# 232_CAN.net
KiCad netlist of a schematic drawn in Altium Designer
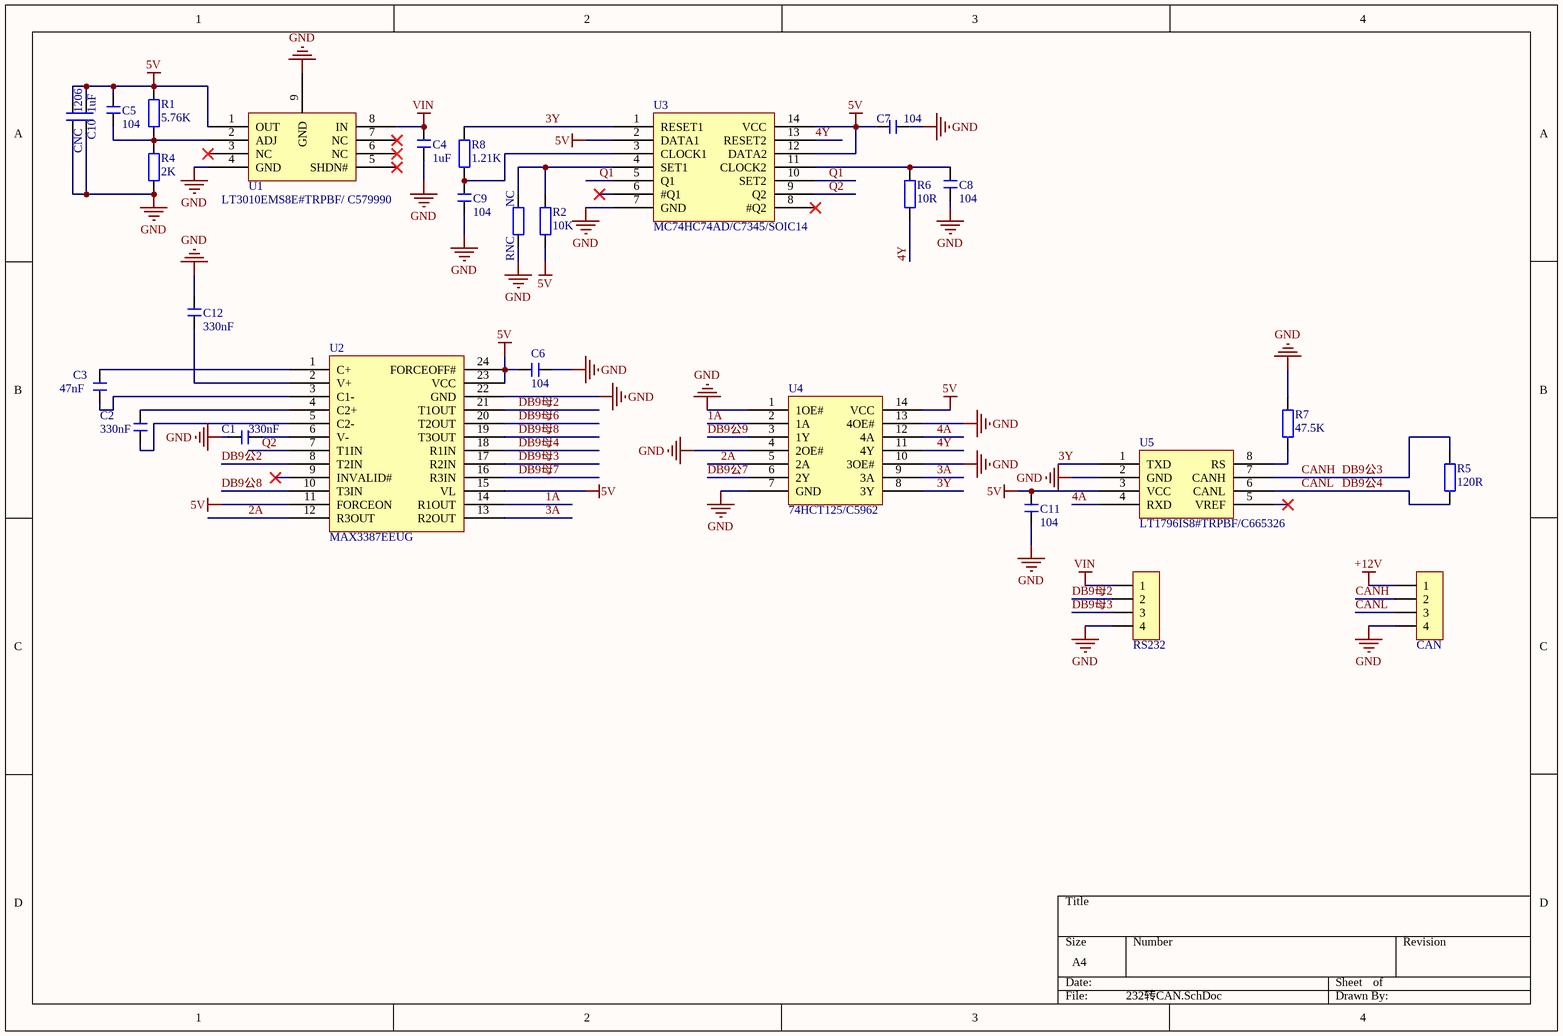
[diagram p0: 232转CAN.SchDoc]

(export (version "E")
  (design (tool "Eeschema 10.0.6"))
  (components
    (comp (ref "C1")
      (value "330nF")
      (footprint "C0603_L")
      (description "独石电容")
      (fields (field (name "版权归属") "封装库来自淘宝 ID：黄晶宝石"))
      (libsource (lib "0.1 - 电阻-电容-电感") (part "C-MLCC"))
    )
    (comp (ref "C2")
      (value "330nF")
      (footprint "C0603_L")
      (description "独石电容")
      (fields (field (name "版权归属") "封装库来自淘宝 ID：黄晶宝石"))
      (libsource (lib "0.1 - 电阻-电容-电感") (part "C-MLCC"))
    )
    (comp (ref "C3")
      (value "47nF")
      (footprint "C0603_L")
      (description "独石电容")
      (fields (field (name "版权归属") "封装库来自淘宝 ID：黄晶宝石"))
      (libsource (lib "0.1 - 电阻-电容-电感") (part "C-MLCC"))
    )
    (comp (ref "C4")
      (value "1uF")
      (footprint "C0603_L")
      (description "独石电容")
      (fields (field (name "版权归属") "封装库来自淘宝 ID：黄晶宝石"))
      (libsource (lib "0.1 - 电阻-电容-电感") (part "C-MLCC"))
    )
    (comp (ref "C5")
      (value "104")
      (footprint "C0603_L")
      (description "贴片电容")
      (libsource (lib "0.1 - 电阻-电容-电感") (part "C"))
    )
    (comp (ref "C6")
      (value "104")
      (footprint "C0603_L")
      (description "独石电容")
      (fields (field (name "版权归属") "封装库来自淘宝 ID：黄晶宝石"))
      (libsource (lib "0.1 - 电阻-电容-电感") (part "C-MLCC"))
    )
    (comp (ref "C7")
      (value "104")
      (footprint "C0603_L")
      (description "独石电容")
      (fields (field (name "版权归属") "封装库来自淘宝 ID：黄晶宝石"))
      (libsource (lib "0.1 - 电阻-电容-电感") (part "C-MLCC"))
    )
    (comp (ref "C8")
      (value "104")
      (footprint "C0603_L")
      (description "独石电容")
      (fields (field (name "版权归属") "封装库来自淘宝 ID：黄晶宝石"))
      (libsource (lib "0.1 - 电阻-电容-电感") (part "C-MLCC"))
    )
    (comp (ref "C9")
      (value "104")
      (footprint "C0603_L")
      (description "独石电容")
      (fields (field (name "版权归属") "封装库来自淘宝 ID：黄晶宝石"))
      (libsource (lib "0.1 - 电阻-电容-电感") (part "C-MLCC"))
    )
    (comp (ref "C10")
      (value "1uF")
      (footprint "C0603_L")
      (description "独石电容")
      (fields (field (name "版权归属") "封装库来自淘宝 ID：黄晶宝石"))
      (libsource (lib "0.1 - 电阻-电容-电感") (part "C-MLCC"))
    )
    (comp (ref "C11")
      (value "104")
      (footprint "C0603_L")
      (description "独石电容")
      (fields (field (name "版权归属") "封装库来自淘宝 ID：黄晶宝石"))
      (libsource (lib "0.1 - 电阻-电容-电感") (part "C-MLCC"))
    )
    (comp (ref "C12")
      (value "330nF")
      (footprint "C0603_L")
      (description "独石电容")
      (fields (field (name "版权归属") "封装库来自淘宝 ID：黄晶宝石"))
      (libsource (lib "0.1 - 电阻-电容-电感") (part "C-MLCC"))
    )
    (comp (ref "CAN")
      (value "HDR-1X4")
      (footprint "HDR2.54-LI-4P")
      (description "4P接插件")
      (fields (field (name "版权归属") "封装库来自淘宝 ID：黄晶宝石"))
      (libsource (lib "5.4 - 接插件-脚距2.54 (100mil) ") (part "Header 4"))
    )
    (comp (ref "CNC")
      (value "1206")
      (footprint "C1206_L")
      (description "独石电容")
      (fields (field (name "版权归属") "封装库来自淘宝 ID：黄晶宝石"))
      (libsource (lib "0.1 - 电阻-电容-电感") (part "C-MLCC"))
    )
    (comp (ref "R1")
      (value "5.76K")
      (footprint "R0603_L")
      (description "贴片电阻")
      (fields (field (name "版权归属") "来自淘宝 ID：黄晶宝石"))
      (libsource (lib "0.1 - 电阻-电容-电感") (part "R"))
    )
    (comp (ref "R2")
      (value "10K")
      (footprint "R0603_L")
      (description "贴片电阻")
      (fields (field (name "版权归属") "来自淘宝 ID：黄晶宝石"))
      (libsource (lib "0.1 - 电阻-电容-电感") (part "R"))
    )
    (comp (ref "R4")
      (value "2K")
      (footprint "R0603_L")
      (description "贴片电阻")
      (fields (field (name "版权归属") "来自淘宝 ID：黄晶宝石"))
      (libsource (lib "0.1 - 电阻-电容-电感") (part "R"))
    )
    (comp (ref "R5")
      (value "120R")
      (footprint "R0603_L")
      (description "贴片电阻")
      (fields (field (name "版权归属") "来自淘宝 ID：黄晶宝石"))
      (libsource (lib "0.1 - 电阻-电容-电感") (part "R"))
    )
    (comp (ref "R6")
      (value "10R")
      (footprint "R0603_L")
      (description "贴片电阻")
      (fields (field (name "版权归属") "来自淘宝 ID：黄晶宝石"))
      (libsource (lib "0.1 - 电阻-电容-电感") (part "R"))
    )
    (comp (ref "R7")
      (value "47.5K")
      (footprint "R0603_L")
      (description "贴片电阻")
      (fields (field (name "版权归属") "来自淘宝 ID：黄晶宝石"))
      (libsource (lib "0.1 - 电阻-电容-电感") (part "R"))
    )
    (comp (ref "R8")
      (value "1.21K")
      (footprint "R0603_L")
      (description "贴片电阻")
      (fields (field (name "版权归属") "来自淘宝 ID：黄晶宝石"))
      (libsource (lib "0.1 - 电阻-电容-电感") (part "R"))
    )
    (comp (ref "RNC")
      (value "NC")
      (footprint "R0603_L")
      (description "贴片电阻")
      (fields (field (name "版权归属") "来自淘宝 ID：黄晶宝石"))
      (libsource (lib "0.1 - 电阻-电容-电感") (part "R"))
    )
    (comp (ref "RS232")
      (value "HDR-1X4")
      (footprint "HDR2.54-LI-4P")
      (description "4P接插件")
      (fields (field (name "版权归属") "封装库来自淘宝 ID：黄晶宝石"))
      (libsource (lib "5.4 - 接插件-脚距2.54 (100mil) ") (part "Header 4"))
    )
    (comp (ref "U1")
      (value "LT3010EMS8E#TRPBF/ C579990")
      (footprint "LT3010EMS8E#TRPBF/sop8-ep")
      (libsource (lib "232转CAN") (part "LT3010EMS8E#TRPBF/ C579990"))
    )
    (comp (ref "U2")
      (value "MAX3387EEUG")
      (footprint "MAX3387EEUG/tssop24")
      (libsource (lib "232转CAN") (part "MAX3387EEUG"))
    )
    (comp (ref "U3")
      (value "MC74HC74AD/C7345/SOIC14")
      (footprint "74HCT125/SOIC14")
      (libsource (lib "232转CAN") (part "MC74HC74AD/C7345/SOIC14"))
    )
    (comp (ref "U4")
      (value "74HCT125/C5962")
      (footprint "74HCT125/SOIC14")
      (libsource (lib "232转CAN") (part "74HCT125/C5962"))
    )
    (comp (ref "U5")
      (value "LT1796IS8#TRPBF/C665326")
      (footprint "LT1796IS8#TRPBF/C665326")
      (libsource (lib "232转CAN") (part "LT1796IS8#TRPBF/C665326"))
    )
  )
  (nets
    (net (code "1") (name "+12V") (class "Default")
      (node (ref "CAN") (pin "1") (pinfunction "1_1") (pintype "passive"))
    )
    (net (code "2") (name "/1A") (class "Default")
      (node (ref "U2") (pin "14") (pinfunction "R1OUT_14") (pintype "passive"))
      (node (ref "U4") (pin "2") (pinfunction "1A_2") (pintype "passive"))
    )
    (net (code "3") (name "/2A") (class "Default")
      (node (ref "U2") (pin "12") (pinfunction "R3OUT_12") (pintype "passive"))
      (node (ref "U4") (pin "5") (pinfunction "2A_5") (pintype "passive"))
    )
    (net (code "4") (name "/3A") (class "Default")
      (node (ref "U2") (pin "13") (pinfunction "R2OUT_13") (pintype "passive"))
      (node (ref "U4") (pin "9") (pinfunction "3A_9") (pintype "passive"))
    )
    (net (code "5") (name "/3Y") (class "Default")
      (node (ref "R8") (pin "1") (pinfunction "1_1") (pintype "passive"))
      (node (ref "U3") (pin "1") (pinfunction "RESET1_1") (pintype "passive"))
      (node (ref "U4") (pin "8") (pinfunction "3Y_8") (pintype "passive"))
      (node (ref "U5") (pin "1") (pinfunction "TXD_1") (pintype "passive"))
    )
    (net (code "6") (name "/4A") (class "Default")
      (node (ref "U4") (pin "12") (pinfunction "4A_12") (pintype "passive"))
      (node (ref "U5") (pin "4") (pinfunction "RXD_4") (pintype "passive"))
    )
    (net (code "7") (name "/4Y") (class "Default")
      (node (ref "R6") (pin "2") (pinfunction "2_2") (pintype "passive"))
      (node (ref "U3") (pin "13") (pinfunction "RESET2_13") (pintype "passive"))
      (node (ref "U4") (pin "11") (pinfunction "4Y_11") (pintype "passive"))
    )
    (net (code "8") (name "/CANH") (class "Default")
      (node (ref "CAN") (pin "2") (pinfunction "2_2") (pintype "passive"))
      (node (ref "R5") (pin "1") (pinfunction "1_1") (pintype "passive"))
      (node (ref "U5") (pin "7") (pinfunction "CANH_7") (pintype "passive"))
    )
    (net (code "9") (name "/CANL") (class "Default")
      (node (ref "CAN") (pin "3") (pinfunction "3_3") (pintype "passive"))
      (node (ref "R5") (pin "2") (pinfunction "2_2") (pintype "passive"))
      (node (ref "U5") (pin "6") (pinfunction "CANL_6") (pintype "passive"))
    )
    (net (code "10") (name "/DB9公2") (class "Default")
      (node (ref "U2") (pin "8") (pinfunction "T2IN_8") (pintype "passive"))
    )
    (net (code "11") (name "/DB9公7") (class "Default")
      (node (ref "U4") (pin "6") (pinfunction "2Y_6") (pintype "passive"))
    )
    (net (code "12") (name "/DB9公8") (class "Default")
      (node (ref "U2") (pin "10") (pinfunction "T3IN_10") (pintype "passive"))
    )
    (net (code "13") (name "/DB9公9") (class "Default")
      (node (ref "U4") (pin "3") (pinfunction "1Y_3") (pintype "passive"))
    )
    (net (code "14") (name "/DB9母2") (class "Default")
      (node (ref "RS232") (pin "2") (pinfunction "2_2") (pintype "passive"))
      (node (ref "U2") (pin "21") (pinfunction "T1OUT_21") (pintype "passive"))
    )
    (net (code "15") (name "/DB9母3") (class "Default")
      (node (ref "RS232") (pin "3") (pinfunction "3_3") (pintype "passive"))
      (node (ref "U2") (pin "17") (pinfunction "R2IN_17") (pintype "passive"))
    )
    (net (code "16") (name "/DB9母4") (class "Default")
      (node (ref "U2") (pin "18") (pinfunction "R1IN_18") (pintype "passive"))
    )
    (net (code "17") (name "/DB9母6") (class "Default")
      (node (ref "U2") (pin "20") (pinfunction "T2OUT_20") (pintype "passive"))
    )
    (net (code "18") (name "/DB9母7") (class "Default")
      (node (ref "U2") (pin "16") (pinfunction "R3IN_16") (pintype "passive"))
    )
    (net (code "19") (name "/DB9母8") (class "Default")
      (node (ref "U2") (pin "19") (pinfunction "T3OUT_19") (pintype "passive"))
    )
    (net (code "20") (name "/Q1") (class "Default")
      (node (ref "U3") (pin "10") (pinfunction "SET2_10") (pintype "passive"))
      (node (ref "U3") (pin "5") (pinfunction "Q1_5") (pintype "passive"))
    )
    (net (code "21") (name "/Q2") (class "Default")
      (node (ref "U2") (pin "7") (pinfunction "T1IN_7") (pintype "passive"))
      (node (ref "U3") (pin "9") (pinfunction "Q2_9") (pintype "passive"))
    )
    (net (code "22") (name "5V") (class "Default")
      (node (ref "C10") (pin "2") (pinfunction "2_2") (pintype "passive"))
      (node (ref "C11") (pin "1") (pinfunction "1_1") (pintype "passive"))
      (node (ref "C5") (pin "2") (pinfunction "2_2") (pintype "passive"))
      (node (ref "C6") (pin "2") (pinfunction "2_2") (pintype "passive"))
      (node (ref "C7") (pin "1") (pinfunction "1_1") (pintype "passive"))
      (node (ref "CNC") (pin "2") (pinfunction "2_2") (pintype "passive"))
      (node (ref "R1") (pin "2") (pinfunction "2_2") (pintype "passive"))
      (node (ref "R2") (pin "2") (pinfunction "2_2") (pintype "passive"))
      (node (ref "U1") (pin "1") (pinfunction "OUT_1") (pintype "passive"))
      (node (ref "U2") (pin "11") (pinfunction "FORCEON_11") (pintype "passive"))
      (node (ref "U2") (pin "15") (pinfunction "VL_15") (pintype "passive"))
      (node (ref "U2") (pin "23") (pinfunction "VCC_23") (pintype "passive"))
      (node (ref "U2") (pin "24") (pinfunction "FORCEOFF#_24") (pintype "passive"))
      (node (ref "U3") (pin "12") (pinfunction "DATA2_12") (pintype "passive"))
      (node (ref "U3") (pin "14") (pinfunction "VCC_14") (pintype "passive"))
      (node (ref "U3") (pin "2") (pinfunction "DATA1_2") (pintype "passive"))
      (node (ref "U4") (pin "14") (pinfunction "VCC_14") (pintype "passive"))
      (node (ref "U5") (pin "3") (pinfunction "VCC_3") (pintype "passive"))
    )
    (net (code "23") (name "GND") (class "Default")
      (node (ref "C1") (pin "2") (pinfunction "2_2") (pintype "passive"))
      (node (ref "C10") (pin "1") (pinfunction "1_1") (pintype "passive"))
      (node (ref "C11") (pin "2") (pinfunction "2_2") (pintype "passive"))
      (node (ref "C12") (pin "2") (pinfunction "2_2") (pintype "passive"))
      (node (ref "C4") (pin "1") (pinfunction "1_1") (pintype "passive"))
      (node (ref "C6") (pin "1") (pinfunction "1_1") (pintype "passive"))
      (node (ref "C7") (pin "2") (pinfunction "2_2") (pintype "passive"))
      (node (ref "C8") (pin "2") (pinfunction "2_2") (pintype "passive"))
      (node (ref "C9") (pin "1") (pinfunction "1_1") (pintype "passive"))
      (node (ref "CAN") (pin "4") (pinfunction "4_4") (pintype "passive"))
      (node (ref "CNC") (pin "1") (pinfunction "1_1") (pintype "passive"))
      (node (ref "R4") (pin "1") (pinfunction "1_1") (pintype "passive"))
      (node (ref "R7") (pin "1") (pinfunction "1_1") (pintype "passive"))
      (node (ref "RNC") (pin "2") (pinfunction "2_2") (pintype "passive"))
      (node (ref "RS232") (pin "4") (pinfunction "4_4") (pintype "passive"))
      (node (ref "U1") (pin "4") (pinfunction "GND_4") (pintype "passive"))
      (node (ref "U1") (pin "9") (pinfunction "GND_9") (pintype "passive"))
      (node (ref "U2") (pin "22") (pinfunction "GND_22") (pintype "passive"))
      (node (ref "U3") (pin "7") (pinfunction "GND_7") (pintype "passive"))
      (node (ref "U4") (pin "1") (pinfunction "1OE#_1") (pintype "passive"))
      (node (ref "U4") (pin "10") (pinfunction "3OE#_10") (pintype "passive"))
      (node (ref "U4") (pin "13") (pinfunction "4OE#_13") (pintype "passive"))
      (node (ref "U4") (pin "4") (pinfunction "2OE#_4") (pintype "passive"))
      (node (ref "U4") (pin "7") (pinfunction "GND_7") (pintype "passive"))
      (node (ref "U5") (pin "2") (pinfunction "GND_2") (pintype "passive"))
    )
    (net (code "24") (name "Net-(U1-ADJ)") (class "Default")
      (node (ref "C5") (pin "1") (pinfunction "1_1") (pintype "passive"))
      (node (ref "R1") (pin "1") (pinfunction "1_1") (pintype "passive"))
      (node (ref "R4") (pin "2") (pinfunction "2_2") (pintype "passive"))
      (node (ref "U1") (pin "2") (pinfunction "ADJ_2") (pintype "passive"))
    )
    (net (code "25") (name "Net-(U2-C+)") (class "Default")
      (node (ref "C3") (pin "2") (pinfunction "2_2") (pintype "passive"))
      (node (ref "U2") (pin "1") (pinfunction "C+_1") (pintype "passive"))
    )
    (net (code "26") (name "Net-(U2-C1-)") (class "Default")
      (node (ref "C3") (pin "1") (pinfunction "1_1") (pintype "passive"))
      (node (ref "U2") (pin "3") (pinfunction "C1-_3") (pintype "passive"))
    )
    (net (code "27") (name "Net-(U2-C2+)") (class "Default")
      (node (ref "C2") (pin "2") (pinfunction "2_2") (pintype "passive"))
      (node (ref "U2") (pin "4") (pinfunction "C2+_4") (pintype "passive"))
    )
    (net (code "28") (name "Net-(U2-C2-)") (class "Default")
      (node (ref "C2") (pin "1") (pinfunction "1_1") (pintype "passive"))
      (node (ref "U2") (pin "5") (pinfunction "C2-_5") (pintype "passive"))
    )
    (net (code "29") (name "Net-(U2-V+)") (class "Default")
      (node (ref "C12") (pin "1") (pinfunction "1_1") (pintype "passive"))
      (node (ref "U2") (pin "2") (pinfunction "V+_2") (pintype "passive"))
    )
    (net (code "30") (name "Net-(U2-V-)") (class "Default")
      (node (ref "C1") (pin "1") (pinfunction "1_1") (pintype "passive"))
      (node (ref "U2") (pin "6") (pinfunction "V-_6") (pintype "passive"))
    )
    (net (code "31") (name "Net-(U3-CLOCK1)") (class "Default")
      (node (ref "C9") (pin "2") (pinfunction "2_2") (pintype "passive"))
      (node (ref "R8") (pin "2") (pinfunction "2_2") (pintype "passive"))
      (node (ref "U3") (pin "3") (pinfunction "CLOCK1_3") (pintype "passive"))
    )
    (net (code "32") (name "Net-(U3-CLOCK2)") (class "Default")
      (node (ref "C8") (pin "1") (pinfunction "1_1") (pintype "passive"))
      (node (ref "R6") (pin "1") (pinfunction "1_1") (pintype "passive"))
      (node (ref "U3") (pin "11") (pinfunction "CLOCK2_11") (pintype "passive"))
    )
    (net (code "33") (name "Net-(U3-SET1)") (class "Default")
      (node (ref "R2") (pin "1") (pinfunction "1_1") (pintype "passive"))
      (node (ref "RNC") (pin "1") (pinfunction "1_1") (pintype "passive"))
      (node (ref "U3") (pin "4") (pinfunction "SET1_4") (pintype "passive"))
    )
    (net (code "34") (name "Net-(U5-RS)") (class "Default")
      (node (ref "R7") (pin "2") (pinfunction "2_2") (pintype "passive"))
      (node (ref "U5") (pin "8") (pinfunction "RS_8") (pintype "passive"))
    )
    (net (code "35") (name "VIN") (class "Default")
      (node (ref "C4") (pin "2") (pinfunction "2_2") (pintype "passive"))
      (node (ref "RS232") (pin "1") (pinfunction "1_1") (pintype "passive"))
      (node (ref "U1") (pin "8") (pinfunction "IN_8") (pintype "passive"))
    )
    (net (code "36") (name "unconnected-(U1-NC-Pad3)") (class "Default")
      (node (ref "U1") (pin "3") (pinfunction "NC_3") (pintype "passive+no_connect"))
    )
    (net (code "37") (name "unconnected-(U1-NC-Pad6)") (class "Default")
      (node (ref "U1") (pin "6") (pinfunction "NC_6") (pintype "passive+no_connect"))
    )
    (net (code "38") (name "unconnected-(U1-NC-Pad7)") (class "Default")
      (node (ref "U1") (pin "7") (pinfunction "NC_7") (pintype "passive+no_connect"))
    )
    (net (code "39") (name "unconnected-(U1-SHDN#-Pad5)") (class "Default")
      (node (ref "U1") (pin "5") (pinfunction "SHDN#_5") (pintype "passive+no_connect"))
    )
    (net (code "40") (name "unconnected-(U2-INVALID#-Pad9)") (class "Default")
      (node (ref "U2") (pin "9") (pinfunction "INVALID#_9") (pintype "passive+no_connect"))
    )
    (net (code "41") (name "unconnected-(U3-#Q1-Pad6)") (class "Default")
      (node (ref "U3") (pin "6") (pinfunction "#Q1_6") (pintype "passive+no_connect"))
    )
    (net (code "42") (name "unconnected-(U3-#Q2-Pad8)") (class "Default")
      (node (ref "U3") (pin "8") (pinfunction "#Q2_8") (pintype "passive+no_connect"))
    )
    (net (code "43") (name "unconnected-(U5-VREF-Pad5)") (class "Default")
      (node (ref "U5") (pin "5") (pinfunction "VREF_5") (pintype "passive+no_connect"))
    )
  )
)
